# FARIOTSsch.net
KiCad netlist of a schematic drawn in EAGLE
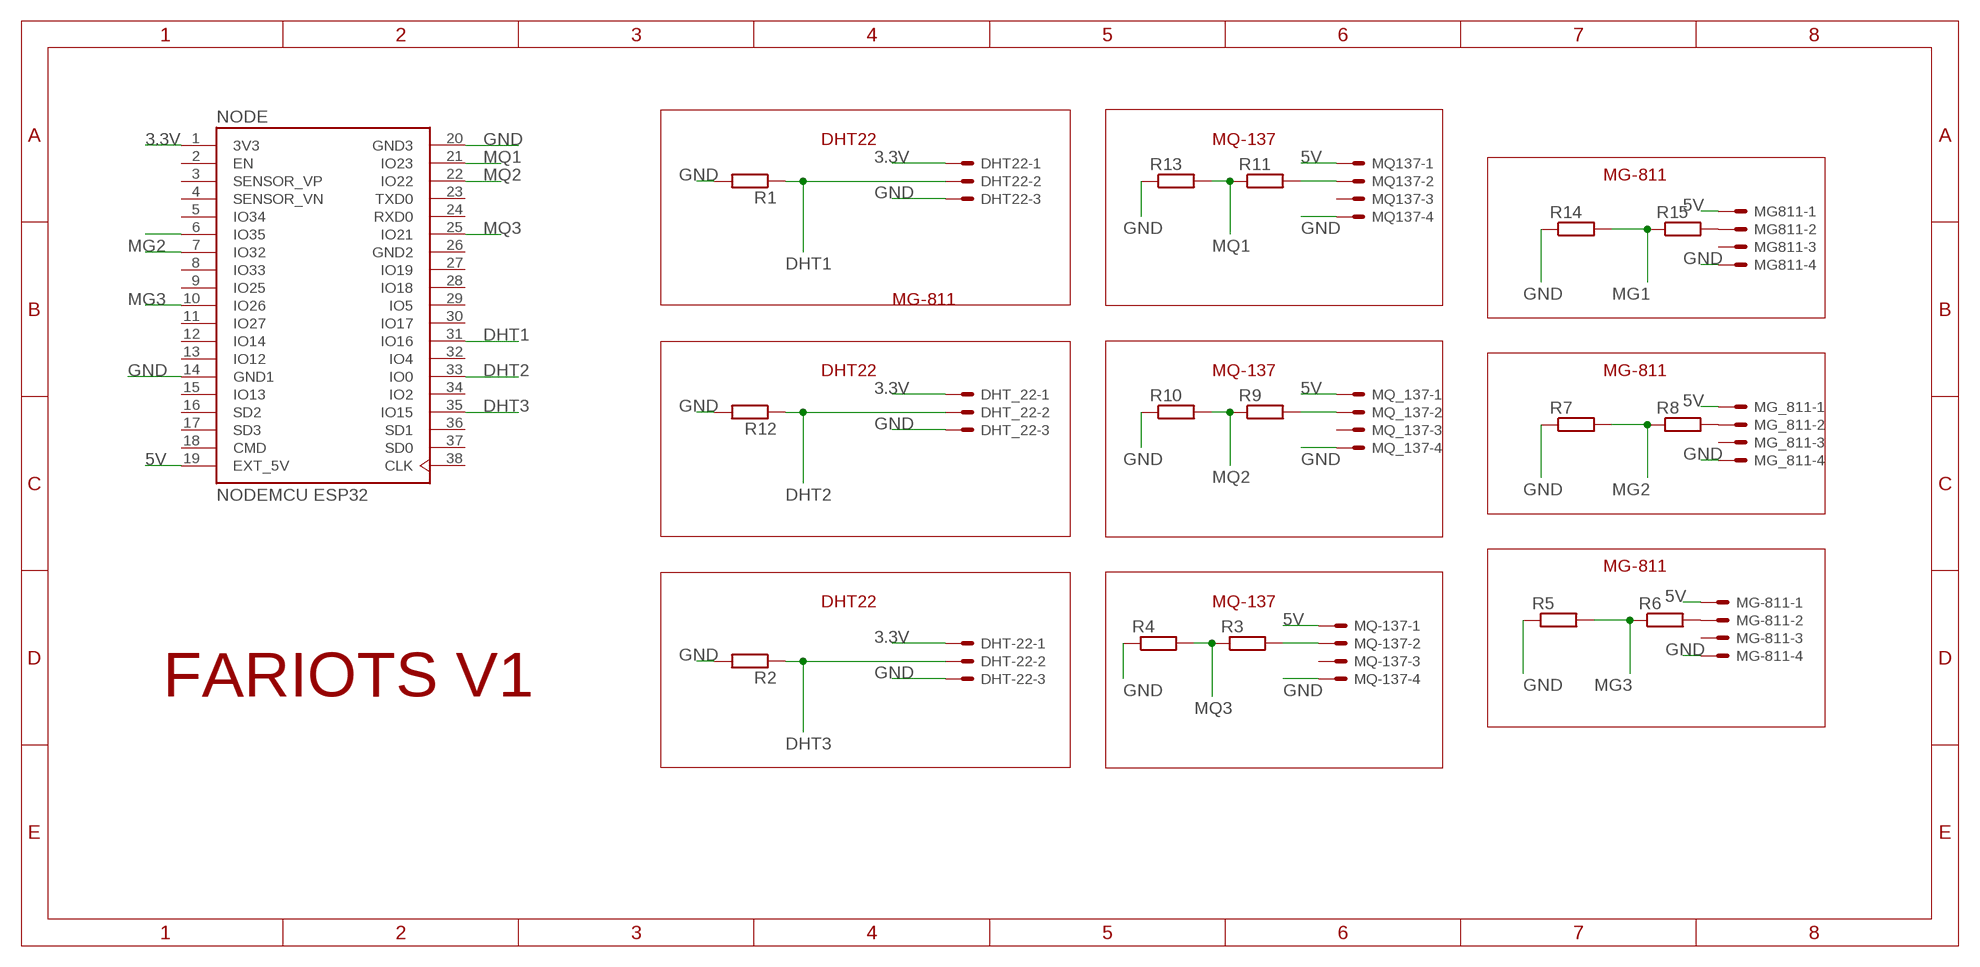
[diagram p0: schematic, sheet 1]

(export (version "E")
  (design (tool "Eeschema 10.0.6"))
  (components
    (comp (ref "DHT-22")
      (value "C-GRID-03-70543")
      (footprint "eagle-import:70543-03")
      (fields (field (name "MF") "MOLEX"))
      (libsource (lib "eagle-import") (part "C-GRID-03-70543"))
    )
    (comp (ref "DHT22")
      (value "C-GRID-03-70543")
      (footprint "eagle-import:70543-03")
      (fields (field (name "MF") "MOLEX"))
      (libsource (lib "eagle-import") (part "C-GRID-03-70543"))
    )
    (comp (ref "DHT_22")
      (value "C-GRID-03-70543")
      (footprint "eagle-import:70543-03")
      (fields (field (name "MF") "MOLEX"))
      (libsource (lib "eagle-import") (part "C-GRID-03-70543"))
    )
    (comp (ref "MG-811")
      (value "C-GRID-04-70543")
      (footprint "eagle-import:70543-04")
      (fields (field (name "MF") "MOLEX"))
      (libsource (lib "eagle-import") (part "C-GRID-04-70543"))
    )
    (comp (ref "MG811")
      (value "C-GRID-04-70543")
      (footprint "eagle-import:70543-04")
      (fields (field (name "MF") "MOLEX"))
      (libsource (lib "eagle-import") (part "C-GRID-04-70543"))
    )
    (comp (ref "MG_811")
      (value "C-GRID-04-70543")
      (footprint "eagle-import:70543-04")
      (fields (field (name "MF") "MOLEX"))
      (libsource (lib "eagle-import") (part "C-GRID-04-70543"))
    )
    (comp (ref "MQ-137")
      (value "C-GRID-04-70543")
      (footprint "eagle-import:70543-04")
      (fields (field (name "MF") "MOLEX"))
      (libsource (lib "eagle-import") (part "C-GRID-04-70543"))
    )
    (comp (ref "MQ137")
      (value "C-GRID-04-70543")
      (footprint "eagle-import:70543-04")
      (fields (field (name "MF") "MOLEX"))
      (libsource (lib "eagle-import") (part "C-GRID-04-70543"))
    )
    (comp (ref "MQ_137")
      (value "C-GRID-04-70543")
      (footprint "eagle-import:70543-04")
      (fields (field (name "MF") "MOLEX"))
      (libsource (lib "eagle-import") (part "C-GRID-04-70543"))
    )
    (comp (ref "NODE")
      (value "NODEMCU ESP32")
      (footprint "eagle-import:MODULE_ESP32-DEVKITC-32D")
      (fields (field (name "MF") "Espressif Systems") (field (name "MP") "ESP32-DEVKITC-32D"))
      (libsource (lib "eagle-import") (part "ESP32-DEVKITC-32D"))
    )
    (comp (ref "R1")
      (value "R-EU_0204/7")
      (footprint "eagle-import:0204_7")
      (libsource (lib "eagle-import") (part "R-EU_0204/7"))
    )
    (comp (ref "R2")
      (value "R-EU_0204/7")
      (footprint "eagle-import:0204_7")
      (libsource (lib "eagle-import") (part "R-EU_0204/7"))
    )
    (comp (ref "R3")
      (value "R-EU_0204/7")
      (footprint "eagle-import:0204_7")
      (libsource (lib "eagle-import") (part "R-EU_0204/7"))
    )
    (comp (ref "R4")
      (value "R-EU_0204/7")
      (footprint "eagle-import:0204_7")
      (libsource (lib "eagle-import") (part "R-EU_0204/7"))
    )
    (comp (ref "R5")
      (value "R-EU_0204/7")
      (footprint "eagle-import:0204_7")
      (libsource (lib "eagle-import") (part "R-EU_0204/7"))
    )
    (comp (ref "R6")
      (value "R-EU_0204/7")
      (footprint "eagle-import:0204_7")
      (libsource (lib "eagle-import") (part "R-EU_0204/7"))
    )
    (comp (ref "R7")
      (value "R-EU_0204/7")
      (footprint "eagle-import:0204_7")
      (libsource (lib "eagle-import") (part "R-EU_0204/7"))
    )
    (comp (ref "R8")
      (value "R-EU_0204/7")
      (footprint "eagle-import:0204_7")
      (libsource (lib "eagle-import") (part "R-EU_0204/7"))
    )
    (comp (ref "R9")
      (value "R-EU_0204/7")
      (footprint "eagle-import:0204_7")
      (libsource (lib "eagle-import") (part "R-EU_0204/7"))
    )
    (comp (ref "R10")
      (value "R-EU_0204/7")
      (footprint "eagle-import:0204_7")
      (libsource (lib "eagle-import") (part "R-EU_0204/7"))
    )
    (comp (ref "R11")
      (value "R-EU_0204/7")
      (footprint "eagle-import:0204_7")
      (libsource (lib "eagle-import") (part "R-EU_0204/7"))
    )
    (comp (ref "R12")
      (value "R-EU_0204/7")
      (footprint "eagle-import:0204_7")
      (libsource (lib "eagle-import") (part "R-EU_0204/7"))
    )
    (comp (ref "R13")
      (value "R-EU_0204/7")
      (footprint "eagle-import:0204_7")
      (libsource (lib "eagle-import") (part "R-EU_0204/7"))
    )
    (comp (ref "R14")
      (value "R-EU_0204/7")
      (footprint "eagle-import:0204_7")
      (libsource (lib "eagle-import") (part "R-EU_0204/7"))
    )
    (comp (ref "R15")
      (value "R-EU_0204/7")
      (footprint "eagle-import:0204_7")
      (libsource (lib "eagle-import") (part "R-EU_0204/7"))
    )
  )
  (nets
    (net (code "1") (name "/3.3V") (class "Default")
      (node (ref "DHT-22") (pin "1") (pinfunction "S_1") (pintype "passive"))
      (node (ref "DHT22") (pin "1") (pinfunction "S_1") (pintype "passive"))
      (node (ref "DHT_22") (pin "1") (pinfunction "S_1") (pintype "passive"))
      (node (ref "NODE") (pin "1") (pinfunction "3V3_1") (pintype "power_in"))
    )
    (net (code "2") (name "/5V") (class "Default")
      (node (ref "MG-811") (pin "1") (pinfunction "S_1") (pintype "passive"))
      (node (ref "MG811") (pin "1") (pinfunction "S_1") (pintype "passive"))
      (node (ref "MG_811") (pin "1") (pinfunction "S_1") (pintype "passive"))
      (node (ref "MQ-137") (pin "1") (pinfunction "S_1") (pintype "passive"))
      (node (ref "MQ137") (pin "1") (pinfunction "S_1") (pintype "passive"))
      (node (ref "MQ_137") (pin "1") (pinfunction "S_1") (pintype "passive"))
      (node (ref "NODE") (pin "19") (pinfunction "EXT_5V_19") (pintype "power_in"))
    )
    (net (code "3") (name "/DHT1") (class "Default")
      (node (ref "DHT22") (pin "2") (pinfunction "S_2") (pintype "passive"))
      (node (ref "NODE") (pin "31") (pinfunction "IO16_31") (pintype "bidirectional"))
      (node (ref "R1") (pin "1") (pinfunction "1_1") (pintype "passive"))
    )
    (net (code "4") (name "/DHT2") (class "Default")
      (node (ref "DHT_22") (pin "2") (pinfunction "S_2") (pintype "passive"))
      (node (ref "NODE") (pin "33") (pinfunction "IO0_33") (pintype "bidirectional"))
      (node (ref "R12") (pin "1") (pinfunction "1_1") (pintype "passive"))
    )
    (net (code "5") (name "/DHT3") (class "Default")
      (node (ref "DHT-22") (pin "2") (pinfunction "S_2") (pintype "passive"))
      (node (ref "NODE") (pin "35") (pinfunction "IO15_35") (pintype "bidirectional"))
      (node (ref "R2") (pin "1") (pinfunction "1_1") (pintype "passive"))
    )
    (net (code "6") (name "/GND") (class "Default")
      (node (ref "DHT-22") (pin "3") (pinfunction "S_3") (pintype "passive"))
      (node (ref "DHT22") (pin "3") (pinfunction "S_3") (pintype "passive"))
      (node (ref "DHT_22") (pin "3") (pinfunction "S_3") (pintype "passive"))
      (node (ref "MG-811") (pin "4") (pinfunction "S_4") (pintype "passive"))
      (node (ref "MG811") (pin "4") (pinfunction "S_4") (pintype "passive"))
      (node (ref "MG_811") (pin "4") (pinfunction "S_4") (pintype "passive"))
      (node (ref "MQ-137") (pin "4") (pinfunction "S_4") (pintype "passive"))
      (node (ref "MQ137") (pin "4") (pinfunction "S_4") (pintype "passive"))
      (node (ref "MQ_137") (pin "4") (pinfunction "S_4") (pintype "passive"))
      (node (ref "NODE") (pin "14") (pinfunction "GND1_14") (pintype "power_in"))
      (node (ref "NODE") (pin "20") (pinfunction "GND3_20") (pintype "power_in"))
      (node (ref "R1") (pin "2") (pinfunction "2_2") (pintype "passive"))
      (node (ref "R10") (pin "1") (pinfunction "1_1") (pintype "passive"))
      (node (ref "R12") (pin "2") (pinfunction "2_2") (pintype "passive"))
      (node (ref "R13") (pin "1") (pinfunction "1_1") (pintype "passive"))
      (node (ref "R14") (pin "1") (pinfunction "1_1") (pintype "passive"))
      (node (ref "R2") (pin "2") (pinfunction "2_2") (pintype "passive"))
      (node (ref "R4") (pin "1") (pinfunction "1_1") (pintype "passive"))
      (node (ref "R5") (pin "1") (pinfunction "1_1") (pintype "passive"))
      (node (ref "R7") (pin "1") (pinfunction "1_1") (pintype "passive"))
    )
    (net (code "7") (name "/GND2") (class "Default")
      (node (ref "NODE") (pin "26") (pinfunction "GND2_26") (pintype "power_in"))
    )
    (net (code "8") (name "/MG1") (class "Default")
      (node (ref "NODE") (pin "6") (pinfunction "IO35_6") (pintype "bidirectional"))
      (node (ref "R14") (pin "2") (pinfunction "2_2") (pintype "passive"))
      (node (ref "R15") (pin "1") (pinfunction "1_1") (pintype "passive"))
    )
    (net (code "9") (name "/MG2") (class "Default")
      (node (ref "NODE") (pin "7") (pinfunction "IO32_7") (pintype "bidirectional"))
      (node (ref "R7") (pin "2") (pinfunction "2_2") (pintype "passive"))
      (node (ref "R8") (pin "1") (pinfunction "1_1") (pintype "passive"))
    )
    (net (code "10") (name "/MG3") (class "Default")
      (node (ref "NODE") (pin "10") (pinfunction "IO26_10") (pintype "bidirectional"))
      (node (ref "R5") (pin "2") (pinfunction "2_2") (pintype "passive"))
      (node (ref "R6") (pin "1") (pinfunction "1_1") (pintype "passive"))
    )
    (net (code "11") (name "/MQ1") (class "Default")
      (node (ref "NODE") (pin "21") (pinfunction "IO23_21") (pintype "bidirectional"))
      (node (ref "R11") (pin "1") (pinfunction "1_1") (pintype "passive"))
      (node (ref "R13") (pin "2") (pinfunction "2_2") (pintype "passive"))
    )
    (net (code "12") (name "/MQ2") (class "Default")
      (node (ref "NODE") (pin "22") (pinfunction "IO22_22") (pintype "bidirectional"))
      (node (ref "R10") (pin "2") (pinfunction "2_2") (pintype "passive"))
      (node (ref "R9") (pin "1") (pinfunction "1_1") (pintype "passive"))
    )
    (net (code "13") (name "/MQ3") (class "Default")
      (node (ref "NODE") (pin "25") (pinfunction "IO21_25") (pintype "bidirectional"))
      (node (ref "R3") (pin "1") (pinfunction "1_1") (pintype "passive"))
      (node (ref "R4") (pin "2") (pinfunction "2_2") (pintype "passive"))
    )
    (net (code "14") (name "Net-(MG-811B-S)") (class "Default")
      (node (ref "MG-811") (pin "2") (pinfunction "S_2") (pintype "passive"))
      (node (ref "R6") (pin "2") (pinfunction "2_2") (pintype "passive"))
    )
    (net (code "15") (name "Net-(MG811B-S)") (class "Default")
      (node (ref "MG811") (pin "2") (pinfunction "S_2") (pintype "passive"))
      (node (ref "R15") (pin "2") (pinfunction "2_2") (pintype "passive"))
    )
    (net (code "16") (name "Net-(MG_811B-S)") (class "Default")
      (node (ref "MG_811") (pin "2") (pinfunction "S_2") (pintype "passive"))
      (node (ref "R8") (pin "2") (pinfunction "2_2") (pintype "passive"))
    )
    (net (code "17") (name "Net-(MQ-137B-S)") (class "Default")
      (node (ref "MQ-137") (pin "2") (pinfunction "S_2") (pintype "passive"))
      (node (ref "R3") (pin "2") (pinfunction "2_2") (pintype "passive"))
    )
    (net (code "18") (name "Net-(MQ137B-S)") (class "Default")
      (node (ref "MQ137") (pin "2") (pinfunction "S_2") (pintype "passive"))
      (node (ref "R11") (pin "2") (pinfunction "2_2") (pintype "passive"))
    )
    (net (code "19") (name "Net-(MQ_137B-S)") (class "Default")
      (node (ref "MQ_137") (pin "2") (pinfunction "S_2") (pintype "passive"))
      (node (ref "R9") (pin "2") (pinfunction "2_2") (pintype "passive"))
    )
    (net (code "20") (name "unconnected-(MG-811C-S-Pad3)") (class "Default")
      (node (ref "MG-811") (pin "3") (pinfunction "S_3") (pintype "passive"))
    )
    (net (code "21") (name "unconnected-(MG811C-S-Pad3)") (class "Default")
      (node (ref "MG811") (pin "3") (pinfunction "S_3") (pintype "passive"))
    )
    (net (code "22") (name "unconnected-(MG_811C-S-Pad3)") (class "Default")
      (node (ref "MG_811") (pin "3") (pinfunction "S_3") (pintype "passive"))
    )
    (net (code "23") (name "unconnected-(MQ-137C-S-Pad3)") (class "Default")
      (node (ref "MQ-137") (pin "3") (pinfunction "S_3") (pintype "passive"))
    )
    (net (code "24") (name "unconnected-(MQ137C-S-Pad3)") (class "Default")
      (node (ref "MQ137") (pin "3") (pinfunction "S_3") (pintype "passive"))
    )
    (net (code "25") (name "unconnected-(MQ_137C-S-Pad3)") (class "Default")
      (node (ref "MQ_137") (pin "3") (pinfunction "S_3") (pintype "passive"))
    )
    (net (code "26") (name "unconnected-(NODE-CLK-Pad38)") (class "Default")
      (node (ref "NODE") (pin "38") (pinfunction "CLK_38") (pintype "input"))
    )
    (net (code "27") (name "unconnected-(NODE-CMD-Pad18)") (class "Default")
      (node (ref "NODE") (pin "18") (pinfunction "CMD_18") (pintype "bidirectional"))
    )
    (net (code "28") (name "unconnected-(NODE-EN-Pad2)") (class "Default")
      (node (ref "NODE") (pin "2") (pinfunction "EN_2") (pintype "input"))
    )
    (net (code "29") (name "unconnected-(NODE-IO2-Pad34)") (class "Default")
      (node (ref "NODE") (pin "34") (pinfunction "IO2_34") (pintype "bidirectional"))
    )
    (net (code "30") (name "unconnected-(NODE-IO4-Pad32)") (class "Default")
      (node (ref "NODE") (pin "32") (pinfunction "IO4_32") (pintype "bidirectional"))
    )
    (net (code "31") (name "unconnected-(NODE-IO5-Pad29)") (class "Default")
      (node (ref "NODE") (pin "29") (pinfunction "IO5_29") (pintype "bidirectional"))
    )
    (net (code "32") (name "unconnected-(NODE-IO12-Pad13)") (class "Default")
      (node (ref "NODE") (pin "13") (pinfunction "IO12_13") (pintype "bidirectional"))
    )
    (net (code "33") (name "unconnected-(NODE-IO13-Pad15)") (class "Default")
      (node (ref "NODE") (pin "15") (pinfunction "IO13_15") (pintype "bidirectional"))
    )
    (net (code "34") (name "unconnected-(NODE-IO14-Pad12)") (class "Default")
      (node (ref "NODE") (pin "12") (pinfunction "IO14_12") (pintype "bidirectional"))
    )
    (net (code "35") (name "unconnected-(NODE-IO17-Pad30)") (class "Default")
      (node (ref "NODE") (pin "30") (pinfunction "IO17_30") (pintype "bidirectional"))
    )
    (net (code "36") (name "unconnected-(NODE-IO18-Pad28)") (class "Default")
      (node (ref "NODE") (pin "28") (pinfunction "IO18_28") (pintype "bidirectional"))
    )
    (net (code "37") (name "unconnected-(NODE-IO19-Pad27)") (class "Default")
      (node (ref "NODE") (pin "27") (pinfunction "IO19_27") (pintype "bidirectional"))
    )
    (net (code "38") (name "unconnected-(NODE-IO25-Pad9)") (class "Default")
      (node (ref "NODE") (pin "9") (pinfunction "IO25_9") (pintype "bidirectional"))
    )
    (net (code "39") (name "unconnected-(NODE-IO27-Pad11)") (class "Default")
      (node (ref "NODE") (pin "11") (pinfunction "IO27_11") (pintype "bidirectional"))
    )
    (net (code "40") (name "unconnected-(NODE-IO33-Pad8)") (class "Default")
      (node (ref "NODE") (pin "8") (pinfunction "IO33_8") (pintype "bidirectional"))
    )
    (net (code "41") (name "unconnected-(NODE-IO34-Pad5)") (class "Default")
      (node (ref "NODE") (pin "5") (pinfunction "IO34_5") (pintype "bidirectional"))
    )
    (net (code "42") (name "unconnected-(NODE-RXD0-Pad24)") (class "Default")
      (node (ref "NODE") (pin "24") (pinfunction "RXD0_24") (pintype "input"))
    )
    (net (code "43") (name "unconnected-(NODE-SD0-Pad37)") (class "Default")
      (node (ref "NODE") (pin "37") (pinfunction "SD0_37") (pintype "bidirectional"))
    )
    (net (code "44") (name "unconnected-(NODE-SD1-Pad36)") (class "Default")
      (node (ref "NODE") (pin "36") (pinfunction "SD1_36") (pintype "bidirectional"))
    )
    (net (code "45") (name "unconnected-(NODE-SD2-Pad16)") (class "Default")
      (node (ref "NODE") (pin "16") (pinfunction "SD2_16") (pintype "bidirectional"))
    )
    (net (code "46") (name "unconnected-(NODE-SD3-Pad17)") (class "Default")
      (node (ref "NODE") (pin "17") (pinfunction "SD3_17") (pintype "bidirectional"))
    )
    (net (code "47") (name "unconnected-(NODE-SENSOR_VN-Pad4)") (class "Default")
      (node (ref "NODE") (pin "4") (pinfunction "SENSOR_VN_4") (pintype "input"))
    )
    (net (code "48") (name "unconnected-(NODE-SENSOR_VP-Pad3)") (class "Default")
      (node (ref "NODE") (pin "3") (pinfunction "SENSOR_VP_3") (pintype "input"))
    )
    (net (code "49") (name "unconnected-(NODE-TXD0-Pad23)") (class "Default")
      (node (ref "NODE") (pin "23") (pinfunction "TXD0_23") (pintype "output"))
    )
  )
)
